# 12-Charging_LED_Indicator.net
KiCad netlist of a schematic drawn in Altium Designer
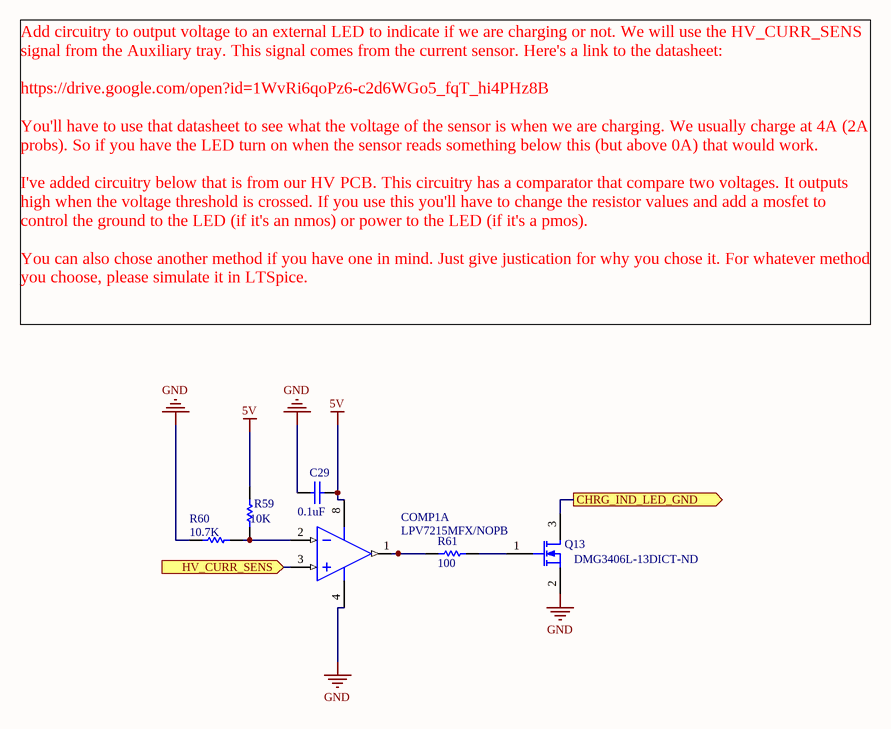
[diagram p0: 12-Charging LED Indicator.SchDoc]

(export (version "E")
  (design (tool "Eeschema 10.0.6"))
  (components
    (comp (ref "C29")
      (value "0.1uF")
      (footprint "1206 (3216 Metric)")
      (description "CGA5L4X7T2W104M160AA: CAP CER 0.1UF 450V X7T 1206")
      (fields (field (name "PUBLISHER") "Altium Limited"))
      (libsource (lib "Miscellaneous Devices") (part "Cap"))
    )
    (comp (ref "COMP1")
      (value "LPV7215MFX/NOPB")
      (footprint "SOIC-SN8_M")
      (description "None")
      (libsource (lib "Altium Content Vault") (part "LO-COMP-MCP6562-IL8"))
    )
    (comp (ref "Q13")
      (value "~")
      (footprint "SOT-23_N")
      (description "N-Channel MOSFET")
      (fields
        (field (name "MANUFACTURER") "Infineon Technologies")
        (field (name "MANUFACTURER PART NUMBER") "IPD075N03L G")
        (field (name "SUPPLIER PART NUMBER 1") "DMG3406L-13DICT-ND")
        (field (name "PUBLISHER") "Altium Limited")
      )
      (libsource (lib "Miscellaneous Devices") (part "MOSFET-N"))
    )
    (comp (ref "R59")
      (value "10K")
      (footprint "1206 (3216 Metric)")
      (fields (field (name "PUBLISHER") "Altium Limited"))
      (libsource (lib "Miscellaneous Devices") (part "Res1"))
    )
    (comp (ref "R60")
      (value "10.7K")
      (footprint "1206 (3216 Metric)")
      (description "KTR18EZPF1501: RES SMD 1.5K OHM 1% 1/4W 1206")
      (fields (field (name "PUBLISHER") "Altium Limited"))
      (libsource (lib "Miscellaneous Devices") (part "Res1"))
    )
    (comp (ref "R61")
      (value "100")
      (footprint "1206 (3216 Metric)")
      (description "KTR18EZPJ101: RES SMD 100 OHM 5% 1/4W 1206")
      (fields (field (name "PUBLISHER") "Altium Limited"))
      (libsource (lib "Miscellaneous Devices") (part "Res1"))
    )
  )
  (nets
    (net (code "1") (name "/CHRG_IND_LED_GND") (class "Default")
      (node (ref "Q13") (pin "3") (pinfunction "D_3") (pintype "passive"))
    )
    (net (code "2") (name "/HV_CURR_SENS") (class "Default")
      (node (ref "COMP1") (pin "3") (pinfunction "INA+_3") (pintype "input"))
    )
    (net (code "3") (name "5V") (class "Default")
      (node (ref "C29") (pin "2") (pinfunction "2_2") (pintype "passive"))
      (node (ref "COMP1") (pin "8") (pinfunction "VDD_8") (pintype "power_in"))
      (node (ref "R59") (pin "1") (pinfunction "1_1") (pintype "passive"))
    )
    (net (code "4") (name "GND") (class "Default")
      (node (ref "C29") (pin "1") (pinfunction "1_1") (pintype "passive"))
      (node (ref "COMP1") (pin "4") (pinfunction "VSS_4") (pintype "power_in"))
      (node (ref "Q13") (pin "2") (pinfunction "S_2") (pintype "passive"))
      (node (ref "R60") (pin "1") (pinfunction "1_1") (pintype "passive"))
    )
    (net (code "5") (name "Net-(COMP1A-INA-)") (class "Default")
      (node (ref "COMP1") (pin "2") (pinfunction "INA-_2") (pintype "input"))
      (node (ref "R59") (pin "2") (pinfunction "2_2") (pintype "passive"))
      (node (ref "R60") (pin "2") (pinfunction "2_2") (pintype "passive"))
    )
    (net (code "6") (name "Net-(COMP1A-OUTA)") (class "Default")
      (node (ref "COMP1") (pin "1") (pinfunction "OUTA_1") (pintype "output"))
      (node (ref "R61") (pin "1") (pinfunction "1_1") (pintype "passive"))
    )
    (net (code "7") (name "Net-(Q13-G)") (class "Default")
      (node (ref "Q13") (pin "1") (pinfunction "G_1") (pintype "passive"))
      (node (ref "R61") (pin "2") (pinfunction "2_2") (pintype "passive"))
    )
  )
)
